# Sheet1.net
KiCad netlist of a schematic drawn in Altium Designer
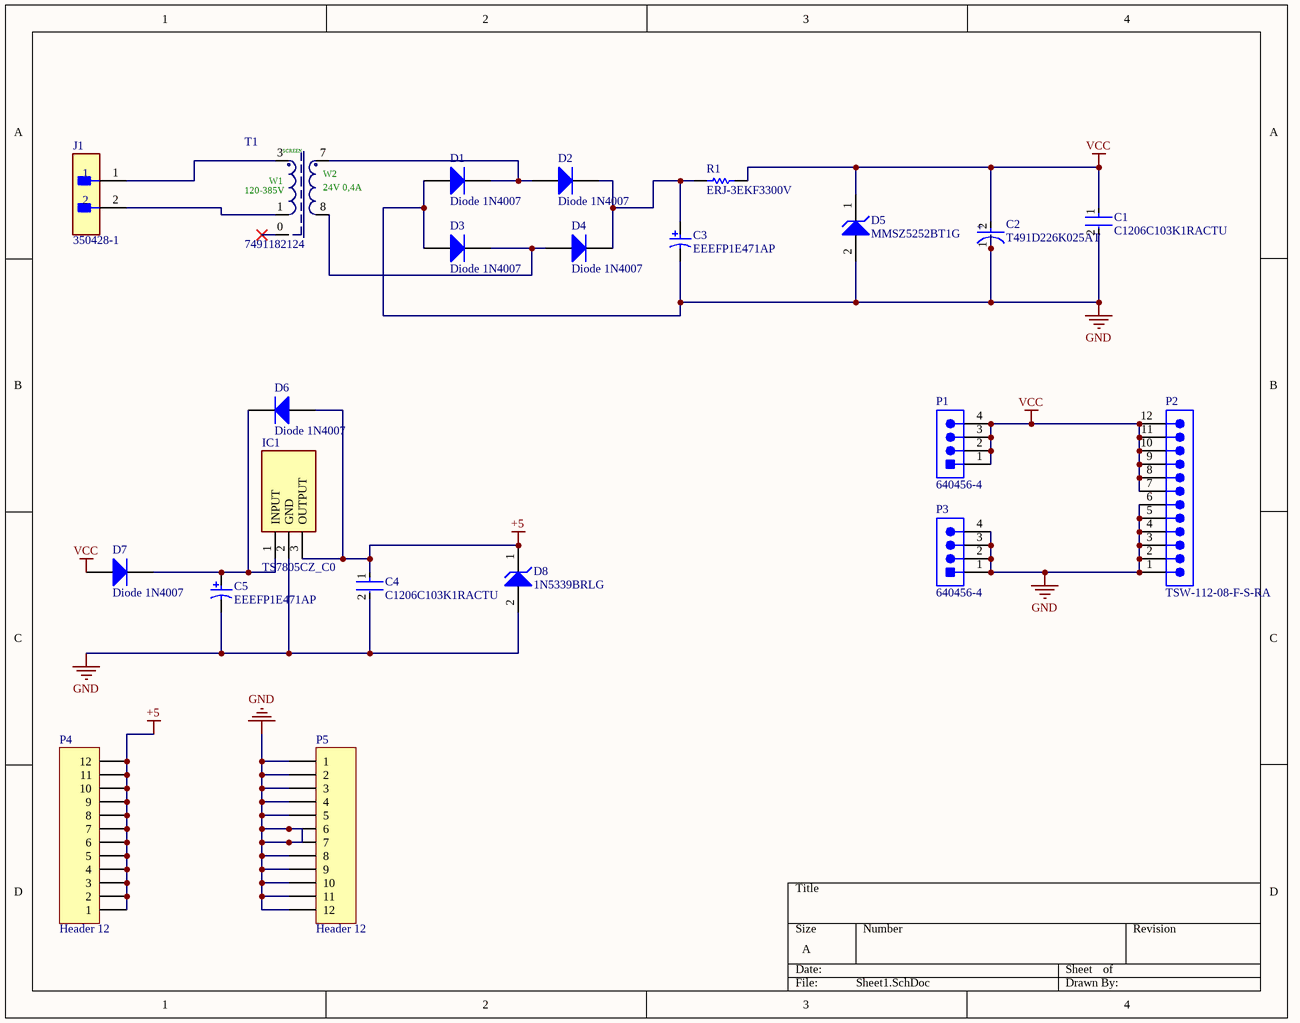
[diagram p0: Sheet1.SchDoc]

(export (version "E")
  (design (tool "Eeschema 10.0.6"))
  (components
    (comp (ref "C1")
      (value "C1206C103K1RACTU")
      (footprint "FP-C1206C-EB-MFG")
      (description "Cap Ceramic 0.01uF 100V X7R 10% SMD 1206 125°C Plastic T/R")
      (fields
        (field (name "MANUFACTURER") "KEMET")
        (field (name "OCTOPART") "https://octopart.com/c1206c103k1ractu-kemet-117927")
      )
      (libsource (lib "Altium Content Vault") (part "b4654b650e69147ec39a6b967a45e02"))
    )
    (comp (ref "C2")
      (value "T491D226K025AT")
      (footprint "FP-T491D226K025AT-MFG")
      (description "CAP TANT 22UF 10% 25V 2917")
      (fields (field (name "TOLERANCE") "10%") (field (name "VOLTAGE") "25V"))
      (libsource (lib "Altium Content Vault") (part "a00bbbee19879c290e62620ae7e47b1"))
    )
    (comp (ref "C3")
      (value "EEEFP1E471AP")
      (footprint "PNSC-FP-V-G_V")
      (fields (field (name "MANUFACTURER") "Panasonic"))
      (libsource (lib "Altium Content Vault") (part "CAP-P-2"))
    )
    (comp (ref "C4")
      (value "C1206C103K1RACTU")
      (footprint "FP-C1206C-EB-MFG")
      (description "Cap Ceramic 0.01uF 100V X7R 10% SMD 1206 125°C Plastic T/R")
      (fields
        (field (name "MANUFACTURER") "KEMET")
        (field (name "OCTOPART") "https://octopart.com/c1206c103k1ractu-kemet-117927")
      )
      (libsource (lib "Altium Content Vault") (part "b4654b650e69147ec39a6b967a45e02"))
    )
    (comp (ref "C5")
      (value "EEEFP1E471AP")
      (footprint "PNSC-FP-V-G_V")
      (fields (field (name "MANUFACTURER") "Panasonic"))
      (libsource (lib "Altium Content Vault") (part "CAP-P-2"))
    )
    (comp (ref "D1")
      (value "Diode 1N4007")
      (footprint "DO-41")
      (description "1 Amp General Purpose Rectifier")
      (fields (field (name "PUBLISHER") "Altium Limited"))
      (libsource (lib "Miscellaneous Devices") (part "Diode 1N4007"))
    )
    (comp (ref "D2")
      (value "Diode 1N4007")
      (footprint "DO-41")
      (description "1 Amp General Purpose Rectifier")
      (fields (field (name "PUBLISHER") "Altium Limited"))
      (libsource (lib "Miscellaneous Devices") (part "Diode 1N4007"))
    )
    (comp (ref "D3")
      (value "Diode 1N4007")
      (footprint "DO-41")
      (description "1 Amp General Purpose Rectifier")
      (fields (field (name "PUBLISHER") "Altium Limited"))
      (libsource (lib "Miscellaneous Devices") (part "Diode 1N4007"))
    )
    (comp (ref "D4")
      (value "Diode 1N4007")
      (footprint "DO-41")
      (description "1 Amp General Purpose Rectifier")
      (fields (field (name "PUBLISHER") "Altium Limited"))
      (libsource (lib "Miscellaneous Devices") (part "Diode 1N4007"))
    )
    (comp (ref "D5")
      (value "MMSZ5252BT1G")
      (footprint "ONSC-SOD-123-2-425-04_V")
      (description "Zener Voltage Regulator, 500 mW, 2-Pin SOD-123, Pb-Free, Tape and Reel")
      (fields (field (name "MANUFACTURER") "On Semiconductor"))
      (libsource (lib "Altium Content Vault") (part "ONSC-K1A2-2"))
    )
    (comp (ref "D6")
      (value "Diode 1N4007")
      (footprint "DO-41")
      (description "1 Amp General Purpose Rectifier")
      (fields (field (name "PUBLISHER") "Altium Limited"))
      (libsource (lib "Miscellaneous Devices") (part "Diode 1N4007"))
    )
    (comp (ref "D7")
      (value "Diode 1N4007")
      (footprint "DO-41")
      (description "1 Amp General Purpose Rectifier")
      (fields (field (name "PUBLISHER") "Altium Limited"))
      (libsource (lib "Miscellaneous Devices") (part "Diode 1N4007"))
    )
    (comp (ref "D8")
      (value "1N5339BRLG")
      (footprint "ONSC-SURMETIC40-2-017AA-01")
      (description "5 W Zener Voltage Regulator, 2-Pin Surmetic(TM) 40, Pb-Free, Tape and Reel")
      (fields (field (name "MANUFACTURER") "On Semiconductor"))
      (libsource (lib "Altium Content Vault") (part "ONSC-K1A2-2"))
    )
    (comp (ref "IC1")
      (value "TS7805CZ_C0")
      (footprint "SamacSys:TO254P483X1000X2285-3P")
      (description "Integrated Circuit")
      (fields
        (field (name "MANUFACTURER_PART_NUMBER") "TS7805CZ C0")
        (field (name "MOUSER PART NUMBER") "821-TS7805CZC0")
      )
      (libsource (lib "*") (part "TS7805CZ_C0"))
    )
    (comp (ref "J1")
      (value "350428-1")
      (footprint "FP-350428-1-MFG")
      (description "CONN HEADER VERT 2POS 6.35MM")
      (fields
        (field (name "OCTOPART") "https://octopart.com/350428-1-te+connectivity-46505355")
        (field (name "MANUFACTURER") "TE Connectivity")
      )
      (libsource (lib "Altium Content Vault") (part "3bc925449376181038e59eaffc5286c"))
    )
    (comp (ref "P1")
      (value "640456-4")
      (footprint "TECO-640456-4")
      (description "Male Header, Pitch 2.54 mm, 1 x 4 Position, Height 10.03 mm, Tail Length 3.56 mm, RoHS, Bulk")
      (fields (field (name "MANUFACTURER") "TE Connectivity"))
      (libsource (lib "Altium Content Vault") (part "CN-1P-M-R4"))
    )
    (comp (ref "P2")
      (value "TSW-112-08-F-S-RA")
      (footprint "SMTC-TSW-112-08-X-S-RA")
      (fields (field (name "MANUFACTURER") "Samtec"))
      (libsource (lib "Altium Content Vault") (part "SMTC-TSW-112-08-X-S-RA"))
    )
    (comp (ref "P3")
      (value "640456-4")
      (footprint "TECO-640456-4")
      (description "Male Header, Pitch 2.54 mm, 1 x 4 Position, Height 10.03 mm, Tail Length 3.56 mm, RoHS, Bulk")
      (fields (field (name "MANUFACTURER") "TE Connectivity"))
      (libsource (lib "Altium Content Vault") (part "CN-1P-M-R4"))
    )
    (comp (ref "P4")
      (value "Header 12")
      (footprint "HDR1X12")
      (description "Header, 12-Pin")
      (fields (field (name "PUBLISHER") "Altium Limited"))
      (libsource (lib "Miscellaneous Connectors") (part "Header 12"))
    )
    (comp (ref "P5")
      (value "Header 12")
      (footprint "HDR1X12")
      (description "Header, 12-Pin")
      (fields (field (name "PUBLISHER") "Altium Limited"))
      (libsource (lib "") (part "Header 12_1"))
    )
    (comp (ref "R1")
      (value "ERJ-3EKF3300V")
      (footprint "RESC1608X55X30LL15T15")
      (description "Chip Resistor, 330 Ohm, +/- 1%, 0.1 W, -55 to 155 degC, 0603 (1608 Metric), RoHS, Tape and Reel")
      (libsource (lib "Altium Content Vault") (part "RES-2"))
    )
    (comp (ref "T1")
      (value "7491182124")
      (footprint "EE16_8_5 (EF16)")
      (description "Off-Line Transformer WE-UNIT , L=0.9mH")
      (fields (field (name "MANUFACTURER") "Wuerth Elektronik"))
      (libsource (lib "Altium Content Vault") (part "WE-7491182124"))
    )
  )
  (nets
    (net (code "1") (name "+5") (class "Default")
      (node (ref "C4") (pin "1") (pinfunction "1_1") (pintype "passive"))
      (node (ref "D6") (pin "1") (pinfunction "A_1") (pintype "passive"))
      (node (ref "D8") (pin "1") (pinfunction "K_1") (pintype "passive"))
      (node (ref "IC1") (pin "3") (pinfunction "OUTPUT_3") (pintype "passive"))
      (node (ref "P4") (pin "1") (pinfunction "1_1") (pintype "passive"))
      (node (ref "P4") (pin "10") (pinfunction "10_10") (pintype "passive"))
      (node (ref "P4") (pin "11") (pinfunction "11_11") (pintype "passive"))
      (node (ref "P4") (pin "12") (pinfunction "12_12") (pintype "passive"))
      (node (ref "P4") (pin "2") (pinfunction "2_2") (pintype "passive"))
      (node (ref "P4") (pin "3") (pinfunction "3_3") (pintype "passive"))
      (node (ref "P4") (pin "4") (pinfunction "4_4") (pintype "passive"))
      (node (ref "P4") (pin "5") (pinfunction "5_5") (pintype "passive"))
      (node (ref "P4") (pin "6") (pinfunction "6_6") (pintype "passive"))
      (node (ref "P4") (pin "7") (pinfunction "7_7") (pintype "passive"))
      (node (ref "P4") (pin "8") (pinfunction "8_8") (pintype "passive"))
      (node (ref "P4") (pin "9") (pinfunction "9_9") (pintype "passive"))
    )
    (net (code "2") (name "GND") (class "Default")
      (node (ref "C1") (pin "2") (pinfunction "2_2") (pintype "passive"))
      (node (ref "C2") (pin "1") (pinfunction "C_1") (pintype "passive"))
      (node (ref "C3") (pin "2") (pinfunction "2_2") (pintype "passive"))
      (node (ref "C4") (pin "2") (pinfunction "2_2") (pintype "passive"))
      (node (ref "C5") (pin "2") (pinfunction "2_2") (pintype "passive"))
      (node (ref "D1") (pin "1") (pinfunction "A_1") (pintype "passive"))
      (node (ref "D3") (pin "1") (pinfunction "A_1") (pintype "passive"))
      (node (ref "D5") (pin "2") (pinfunction "A_2") (pintype "passive"))
      (node (ref "D8") (pin "2") (pinfunction "A_2") (pintype "passive"))
      (node (ref "IC1") (pin "2") (pinfunction "GND_2") (pintype "passive"))
      (node (ref "P2") (pin "1") (pinfunction "1_1") (pintype "passive"))
      (node (ref "P2") (pin "2") (pinfunction "2_2") (pintype "passive"))
      (node (ref "P2") (pin "3") (pinfunction "3_3") (pintype "passive"))
      (node (ref "P2") (pin "4") (pinfunction "4_4") (pintype "passive"))
      (node (ref "P2") (pin "5") (pinfunction "5_5") (pintype "passive"))
      (node (ref "P2") (pin "6") (pinfunction "6_6") (pintype "passive"))
      (node (ref "P3") (pin "1") (pinfunction "1_1") (pintype "passive"))
      (node (ref "P3") (pin "2") (pinfunction "2_2") (pintype "passive"))
      (node (ref "P3") (pin "3") (pinfunction "3_3") (pintype "passive"))
      (node (ref "P3") (pin "4") (pinfunction "4_4") (pintype "passive"))
      (node (ref "P5") (pin "1") (pinfunction "1_1") (pintype "passive"))
      (node (ref "P5") (pin "10") (pinfunction "10_10") (pintype "passive"))
      (node (ref "P5") (pin "11") (pinfunction "11_11") (pintype "passive"))
      (node (ref "P5") (pin "12") (pinfunction "12_12") (pintype "passive"))
      (node (ref "P5") (pin "2") (pinfunction "2_2") (pintype "passive"))
      (node (ref "P5") (pin "3") (pinfunction "3_3") (pintype "passive"))
      (node (ref "P5") (pin "4") (pinfunction "4_4") (pintype "passive"))
      (node (ref "P5") (pin "5") (pinfunction "5_5") (pintype "passive"))
      (node (ref "P5") (pin "6") (pinfunction "6_6") (pintype "passive"))
      (node (ref "P5") (pin "7") (pinfunction "7_7") (pintype "passive"))
      (node (ref "P5") (pin "8") (pinfunction "8_8") (pintype "passive"))
      (node (ref "P5") (pin "9") (pinfunction "9_9") (pintype "passive"))
    )
    (net (code "3") (name "Net-(D1-K)") (class "Default")
      (node (ref "D1") (pin "2") (pinfunction "K_2") (pintype "passive"))
      (node (ref "D2") (pin "1") (pinfunction "A_1") (pintype "passive"))
      (node (ref "T1") (pin "7") (pinfunction "7_7") (pintype "passive"))
    )
    (net (code "4") (name "Net-(D2-K)") (class "Default")
      (node (ref "C3") (pin "1") (pinfunction "1_1") (pintype "passive"))
      (node (ref "D2") (pin "2") (pinfunction "K_2") (pintype "passive"))
      (node (ref "D4") (pin "2") (pinfunction "K_2") (pintype "passive"))
      (node (ref "R1") (pin "1") (pinfunction "1_1") (pintype "passive"))
    )
    (net (code "5") (name "Net-(D3-K)") (class "Default")
      (node (ref "D3") (pin "2") (pinfunction "K_2") (pintype "passive"))
      (node (ref "D4") (pin "1") (pinfunction "A_1") (pintype "passive"))
      (node (ref "T1") (pin "8") (pinfunction "8_8") (pintype "passive"))
    )
    (net (code "6") (name "Net-(D6-K)") (class "Default")
      (node (ref "C5") (pin "1") (pinfunction "1_1") (pintype "passive"))
      (node (ref "D6") (pin "2") (pinfunction "K_2") (pintype "passive"))
      (node (ref "D7") (pin "2") (pinfunction "K_2") (pintype "passive"))
      (node (ref "IC1") (pin "1") (pinfunction "INPUT_1") (pintype "passive"))
    )
    (net (code "7") (name "Net-(J1-Pad1)") (class "Default")
      (node (ref "J1") (pin "1") (pinfunction "1_1") (pintype "passive"))
      (node (ref "T1") (pin "3") (pinfunction "3_3") (pintype "passive"))
    )
    (net (code "8") (name "Net-(J1-Pad2)") (class "Default")
      (node (ref "J1") (pin "2") (pinfunction "2_2") (pintype "passive"))
      (node (ref "T1") (pin "1") (pinfunction "1_1") (pintype "passive"))
    )
    (net (code "9") (name "VCC") (class "Default")
      (node (ref "C1") (pin "1") (pinfunction "1_1") (pintype "passive"))
      (node (ref "C2") (pin "2") (pinfunction "A_2") (pintype "passive"))
      (node (ref "D5") (pin "1") (pinfunction "K_1") (pintype "passive"))
      (node (ref "D7") (pin "1") (pinfunction "A_1") (pintype "passive"))
      (node (ref "P1") (pin "1") (pinfunction "1_1") (pintype "passive"))
      (node (ref "P1") (pin "2") (pinfunction "2_2") (pintype "passive"))
      (node (ref "P1") (pin "3") (pinfunction "3_3") (pintype "passive"))
      (node (ref "P1") (pin "4") (pinfunction "4_4") (pintype "passive"))
      (node (ref "P2") (pin "10") (pinfunction "10_10") (pintype "passive"))
      (node (ref "P2") (pin "11") (pinfunction "11_11") (pintype "passive"))
      (node (ref "P2") (pin "12") (pinfunction "12_12") (pintype "passive"))
      (node (ref "P2") (pin "7") (pinfunction "7_7") (pintype "passive"))
      (node (ref "P2") (pin "8") (pinfunction "8_8") (pintype "passive"))
      (node (ref "P2") (pin "9") (pinfunction "9_9") (pintype "passive"))
      (node (ref "R1") (pin "2") (pinfunction "2_2") (pintype "passive"))
    )
    (net (code "10") (name "unconnected-(T1-Pad0)") (class "Default")
      (node (ref "T1") (pin "0") (pinfunction "0_0") (pintype "passive+no_connect"))
    )
  )
)
